# untitled.net
KiCad netlist of a schematic drawn in EAGLE
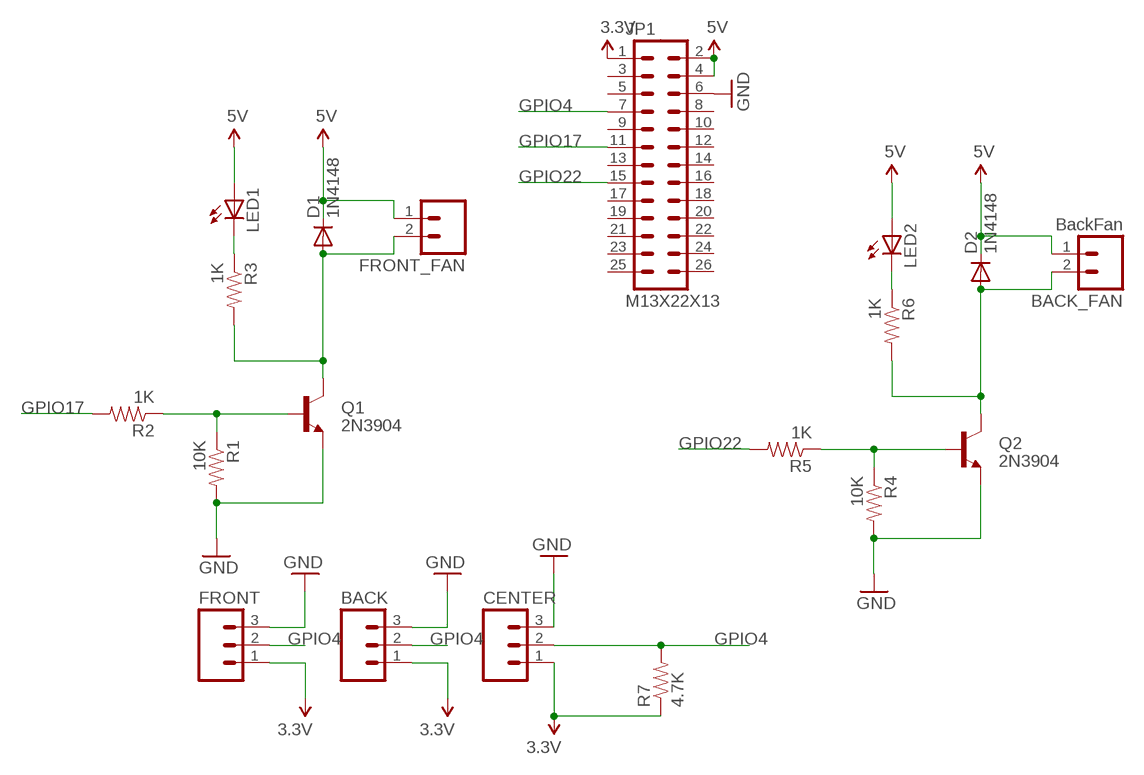
[diagram p0: schematic, sheet 1]

(export (version "E")
  (design (tool "Eeschema 10.0.6"))
  (components
    (comp (ref "BACK")
      (value "M03LOCK_LONGPADS")
      (footprint "eagle-import:1X03_LOCK_LONGPADS")
      (libsource (lib "eagle-import") (part "M03LOCK_LONGPADS"))
    )
    (comp (ref "BACK_FAN")
      (value "BackFan")
      (footprint "eagle-import:1X02_LOCK_LONGPADS")
      (libsource (lib "eagle-import") (part "M02LOCK_LONGPADS"))
    )
    (comp (ref "CENTER")
      (value "M03LOCK_LONGPADS")
      (footprint "eagle-import:1X03_LOCK_LONGPADS")
      (libsource (lib "eagle-import") (part "M03LOCK_LONGPADS"))
    )
    (comp (ref "D1")
      (value "1N4148")
      (footprint "eagle-import:DIODE-1N4148")
      (libsource (lib "eagle-import") (part "DIODE1N4148"))
    )
    (comp (ref "D2")
      (value "1N4148")
      (footprint "eagle-import:DIODE-1N4148")
      (libsource (lib "eagle-import") (part "DIODE1N4148"))
    )
    (comp (ref "FRONT")
      (value "M03LOCK_LONGPADS")
      (footprint "eagle-import:1X03_LOCK_LONGPADS")
      (libsource (lib "eagle-import") (part "M03LOCK_LONGPADS"))
    )
    (comp (ref "FRONT_FAN")
      (value "M02LOCK_LONGPADS")
      (footprint "eagle-import:1X02_LOCK_LONGPADS")
      (libsource (lib "eagle-import") (part "M02LOCK_LONGPADS"))
    )
    (comp (ref "JP1")
      (value "M13X22X13")
      (footprint "eagle-import:2X13")
      (libsource (lib "eagle-import") (part "M13X22X13"))
    )
    (comp (ref "LED1")
      (value "LED5MM")
      (footprint "eagle-import:LED5MM")
      (libsource (lib "eagle-import") (part "LED5MM"))
    )
    (comp (ref "LED2")
      (value "LED5MM")
      (footprint "eagle-import:LED5MM")
      (libsource (lib "eagle-import") (part "LED5MM"))
    )
    (comp (ref "Q1")
      (value "2N3904")
      (footprint "eagle-import:TO-92")
      (libsource (lib "eagle-import") (part "TRANSISTOR_NPNTO92"))
    )
    (comp (ref "Q2")
      (value "2N3904")
      (footprint "eagle-import:TO-92")
      (libsource (lib "eagle-import") (part "TRANSISTOR_NPNTO92"))
    )
    (comp (ref "R1")
      (value "10K")
      (footprint "eagle-import:0805")
      (libsource (lib "eagle-import") (part "RESISTOR0805-RES"))
    )
    (comp (ref "R2")
      (value "1K")
      (footprint "eagle-import:0805")
      (libsource (lib "eagle-import") (part "RESISTOR0805-RES"))
    )
    (comp (ref "R3")
      (value "1K")
      (footprint "eagle-import:0805")
      (libsource (lib "eagle-import") (part "RESISTOR0805-RES"))
    )
    (comp (ref "R4")
      (value "10K")
      (footprint "eagle-import:0805")
      (libsource (lib "eagle-import") (part "RESISTOR0805-RES"))
    )
    (comp (ref "R5")
      (value "1K")
      (footprint "eagle-import:0805")
      (libsource (lib "eagle-import") (part "RESISTOR0805-RES"))
    )
    (comp (ref "R6")
      (value "1K")
      (footprint "eagle-import:0805")
      (libsource (lib "eagle-import") (part "RESISTOR0805-RES"))
    )
    (comp (ref "R7")
      (value "4.7K")
      (footprint "eagle-import:0805")
      (libsource (lib "eagle-import") (part "RESISTOR0805-RES"))
    )
  )
  (nets
    (net (code "1") (name "/GPIO4") (class "Default")
      (node (ref "BACK") (pin "2") (pinfunction "2_2") (pintype "passive"))
      (node (ref "CENTER") (pin "2") (pinfunction "2_2") (pintype "passive"))
      (node (ref "FRONT") (pin "2") (pinfunction "2_2") (pintype "passive"))
      (node (ref "JP1") (pin "7") (pinfunction "7_7") (pintype "passive"))
      (node (ref "R7") (pin "2") (pinfunction "2_2") (pintype "passive"))
    )
    (net (code "2") (name "/GPIO17") (class "Default")
      (node (ref "JP1") (pin "11") (pinfunction "11_11") (pintype "passive"))
      (node (ref "R2") (pin "2") (pinfunction "2_2") (pintype "passive"))
    )
    (net (code "3") (name "/GPIO22") (class "Default")
      (node (ref "JP1") (pin "15") (pinfunction "15_15") (pintype "passive"))
      (node (ref "R5") (pin "2") (pinfunction "2_2") (pintype "passive"))
    )
    (net (code "4") (name "3.3V") (class "Default")
      (node (ref "BACK") (pin "1") (pinfunction "1_1") (pintype "passive"))
      (node (ref "CENTER") (pin "1") (pinfunction "1_1") (pintype "passive"))
      (node (ref "FRONT") (pin "1") (pinfunction "1_1") (pintype "passive"))
      (node (ref "JP1") (pin "1") (pinfunction "1_1") (pintype "passive"))
      (node (ref "R7") (pin "1") (pinfunction "1_1") (pintype "passive"))
    )
    (net (code "5") (name "5V") (class "Default")
      (node (ref "BACK_FAN") (pin "1") (pinfunction "1_1") (pintype "passive"))
      (node (ref "D1") (pin "C") (pinfunction "C_C") (pintype "passive"))
      (node (ref "D2") (pin "C") (pinfunction "C_C") (pintype "passive"))
      (node (ref "FRONT_FAN") (pin "1") (pinfunction "1_1") (pintype "passive"))
      (node (ref "JP1") (pin "2") (pinfunction "2_2") (pintype "passive"))
      (node (ref "JP1") (pin "4") (pinfunction "4_4") (pintype "passive"))
      (node (ref "LED1") (pin "A") (pinfunction "A_A") (pintype "passive"))
      (node (ref "LED2") (pin "A") (pinfunction "A_A") (pintype "passive"))
    )
    (net (code "6") (name "GND") (class "Default")
      (node (ref "BACK") (pin "3") (pinfunction "3_3") (pintype "passive"))
      (node (ref "CENTER") (pin "3") (pinfunction "3_3") (pintype "passive"))
      (node (ref "FRONT") (pin "3") (pinfunction "3_3") (pintype "passive"))
      (node (ref "JP1") (pin "6") (pinfunction "6_6") (pintype "passive"))
      (node (ref "Q1") (pin "1") (pinfunction "E_1") (pintype "passive"))
      (node (ref "Q2") (pin "1") (pinfunction "E_1") (pintype "passive"))
      (node (ref "R1") (pin "2") (pinfunction "2_2") (pintype "passive"))
      (node (ref "R4") (pin "2") (pinfunction "2_2") (pintype "passive"))
    )
    (net (code "7") (name "Net-(LED1-C)") (class "Default")
      (node (ref "LED1") (pin "K") (pinfunction "C_K") (pintype "passive"))
      (node (ref "R3") (pin "1") (pinfunction "1_1") (pintype "passive"))
    )
    (net (code "8") (name "Net-(LED2-C)") (class "Default")
      (node (ref "LED2") (pin "K") (pinfunction "C_K") (pintype "passive"))
      (node (ref "R6") (pin "1") (pinfunction "1_1") (pintype "passive"))
    )
    (net (code "9") (name "Net-(Q1-B)") (class "Default")
      (node (ref "Q1") (pin "2") (pinfunction "B_2") (pintype "passive"))
      (node (ref "R1") (pin "1") (pinfunction "1_1") (pintype "passive"))
      (node (ref "R2") (pin "1") (pinfunction "1_1") (pintype "passive"))
    )
    (net (code "10") (name "Net-(Q1-C)") (class "Default")
      (node (ref "D1") (pin "A") (pinfunction "A_A") (pintype "passive"))
      (node (ref "FRONT_FAN") (pin "2") (pinfunction "2_2") (pintype "passive"))
      (node (ref "Q1") (pin "3") (pinfunction "C_3") (pintype "passive"))
      (node (ref "R3") (pin "2") (pinfunction "2_2") (pintype "passive"))
    )
    (net (code "11") (name "Net-(Q2-B)") (class "Default")
      (node (ref "Q2") (pin "2") (pinfunction "B_2") (pintype "passive"))
      (node (ref "R4") (pin "1") (pinfunction "1_1") (pintype "passive"))
      (node (ref "R5") (pin "1") (pinfunction "1_1") (pintype "passive"))
    )
    (net (code "12") (name "Net-(Q2-C)") (class "Default")
      (node (ref "BACK_FAN") (pin "2") (pinfunction "2_2") (pintype "passive"))
      (node (ref "D2") (pin "A") (pinfunction "A_A") (pintype "passive"))
      (node (ref "Q2") (pin "3") (pinfunction "C_3") (pintype "passive"))
      (node (ref "R6") (pin "2") (pinfunction "2_2") (pintype "passive"))
    )
    (net (code "13") (name "unconnected-(JP1-Pad3)") (class "Default")
      (node (ref "JP1") (pin "3") (pinfunction "3_3") (pintype "passive"))
    )
    (net (code "14") (name "unconnected-(JP1-Pad5)") (class "Default")
      (node (ref "JP1") (pin "5") (pinfunction "5_5") (pintype "passive"))
    )
    (net (code "15") (name "unconnected-(JP1-Pad8)") (class "Default")
      (node (ref "JP1") (pin "8") (pinfunction "8_8") (pintype "passive"))
    )
    (net (code "16") (name "unconnected-(JP1-Pad9)") (class "Default")
      (node (ref "JP1") (pin "9") (pinfunction "9_9") (pintype "passive"))
    )
    (net (code "17") (name "unconnected-(JP1-Pad10)") (class "Default")
      (node (ref "JP1") (pin "10") (pinfunction "10_10") (pintype "passive"))
    )
    (net (code "18") (name "unconnected-(JP1-Pad12)") (class "Default")
      (node (ref "JP1") (pin "12") (pinfunction "12_12") (pintype "passive"))
    )
    (net (code "19") (name "unconnected-(JP1-Pad13)") (class "Default")
      (node (ref "JP1") (pin "13") (pinfunction "13_13") (pintype "passive"))
    )
    (net (code "20") (name "unconnected-(JP1-Pad14)") (class "Default")
      (node (ref "JP1") (pin "14") (pinfunction "14_14") (pintype "passive"))
    )
    (net (code "21") (name "unconnected-(JP1-Pad16)") (class "Default")
      (node (ref "JP1") (pin "16") (pinfunction "16_16") (pintype "passive"))
    )
    (net (code "22") (name "unconnected-(JP1-Pad17)") (class "Default")
      (node (ref "JP1") (pin "17") (pinfunction "17_17") (pintype "passive"))
    )
    (net (code "23") (name "unconnected-(JP1-Pad18)") (class "Default")
      (node (ref "JP1") (pin "18") (pinfunction "18_18") (pintype "passive"))
    )
    (net (code "24") (name "unconnected-(JP1-Pad19)") (class "Default")
      (node (ref "JP1") (pin "19") (pinfunction "19_19") (pintype "passive"))
    )
    (net (code "25") (name "unconnected-(JP1-Pad20)") (class "Default")
      (node (ref "JP1") (pin "20") (pinfunction "20_20") (pintype "passive"))
    )
    (net (code "26") (name "unconnected-(JP1-Pad21)") (class "Default")
      (node (ref "JP1") (pin "21") (pinfunction "21_21") (pintype "passive"))
    )
    (net (code "27") (name "unconnected-(JP1-Pad22)") (class "Default")
      (node (ref "JP1") (pin "22") (pinfunction "22_22") (pintype "passive"))
    )
    (net (code "28") (name "unconnected-(JP1-Pad23)") (class "Default")
      (node (ref "JP1") (pin "23") (pinfunction "23_23") (pintype "passive"))
    )
    (net (code "29") (name "unconnected-(JP1-Pad24)") (class "Default")
      (node (ref "JP1") (pin "24") (pinfunction "24_24") (pintype "passive"))
    )
    (net (code "30") (name "unconnected-(JP1-Pad25)") (class "Default")
      (node (ref "JP1") (pin "25") (pinfunction "25_25") (pintype "passive"))
    )
    (net (code "31") (name "unconnected-(JP1-Pad26)") (class "Default")
      (node (ref "JP1") (pin "26") (pinfunction "26_26") (pintype "passive"))
    )
  )
)
